# 4_Channel_ADC.net
KiCad netlist of a schematic drawn in Altium Designer
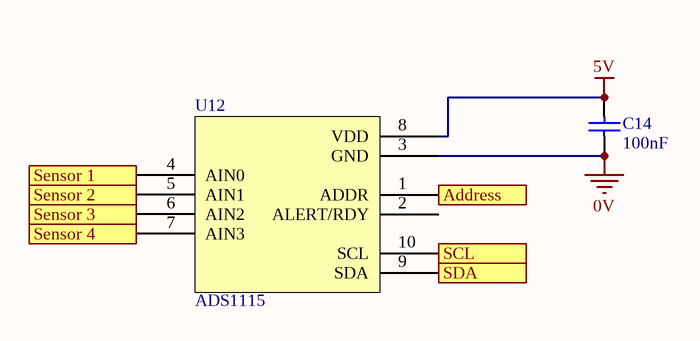
[diagram p0: 4 Channel ADC.SchDoc]

(export (version "E")
  (design (tool "Eeschema 10.0.6"))
  (components
    (comp (ref "C14")
      (value "100nF")
      (footprint "0805")
      (fields
        (field (name "PART NUMBER") "GCM21BR71E104KA37L")
        (field (name "TOLERANCE") "10%")
        (field (name "MANUFACTURER") "muRata")
      )
      (libsource (lib "ts_20-standard-library") (part "Capacitor"))
    )
    (comp (ref "U12")
      (value "ADS1115")
      (footprint "TI 10-VSSOP")
      (description "16 Bit Analog to Digital Converter 2, 4 Input 1 Sigma-Delta 10-VSSOP")
      (fields
        (field (name "MANUFACTURER") "Texas Instruments")
        (field (name "DIGIKEY PART NUMBER") "296-38849-1-ND")
      )
      (libsource (lib "ts_20-standard-library") (part "ADS1115"))
    )
  )
  (nets
    (net (code "1") (name "/Address") (class "Default")
      (node (ref "U12") (pin "1") (pinfunction "ADDR_1") (pintype "passive"))
    )
    (net (code "2") (name "/SCL") (class "Default")
      (node (ref "U12") (pin "10") (pinfunction "SCL_10") (pintype "passive"))
    )
    (net (code "3") (name "/SDA") (class "Default")
      (node (ref "U12") (pin "9") (pinfunction "SDA_9") (pintype "passive"))
    )
    (net (code "4") (name "/Sensor 1") (class "Default")
      (node (ref "U12") (pin "4") (pinfunction "AIN0_4") (pintype "passive"))
    )
    (net (code "5") (name "/Sensor 2") (class "Default")
      (node (ref "U12") (pin "5") (pinfunction "AIN1_5") (pintype "passive"))
    )
    (net (code "6") (name "/Sensor 3") (class "Default")
      (node (ref "U12") (pin "6") (pinfunction "AIN2_6") (pintype "passive"))
    )
    (net (code "7") (name "/Sensor 4") (class "Default")
      (node (ref "U12") (pin "7") (pinfunction "AIN3_7") (pintype "passive"))
    )
    (net (code "8") (name "0V") (class "Default")
      (node (ref "C14") (pin "1") (pinfunction "1_1") (pintype "passive"))
      (node (ref "U12") (pin "3") (pinfunction "GND_3") (pintype "passive"))
    )
    (net (code "9") (name "5V") (class "Default")
      (node (ref "C14") (pin "2") (pinfunction "2_2") (pintype "passive"))
      (node (ref "U12") (pin "8") (pinfunction "VDD_8") (pintype "passive"))
    )
    (net (code "10") (name "unconnected-(U12-ALERT{slash}RDY-Pad2)") (class "Default")
      (node (ref "U12") (pin "2") (pinfunction "ALERT/RDY_2") (pintype "passive"))
    )
  )
)
